# NFC_led_bar.net
KiCad netlist of a schematic drawn in EAGLE
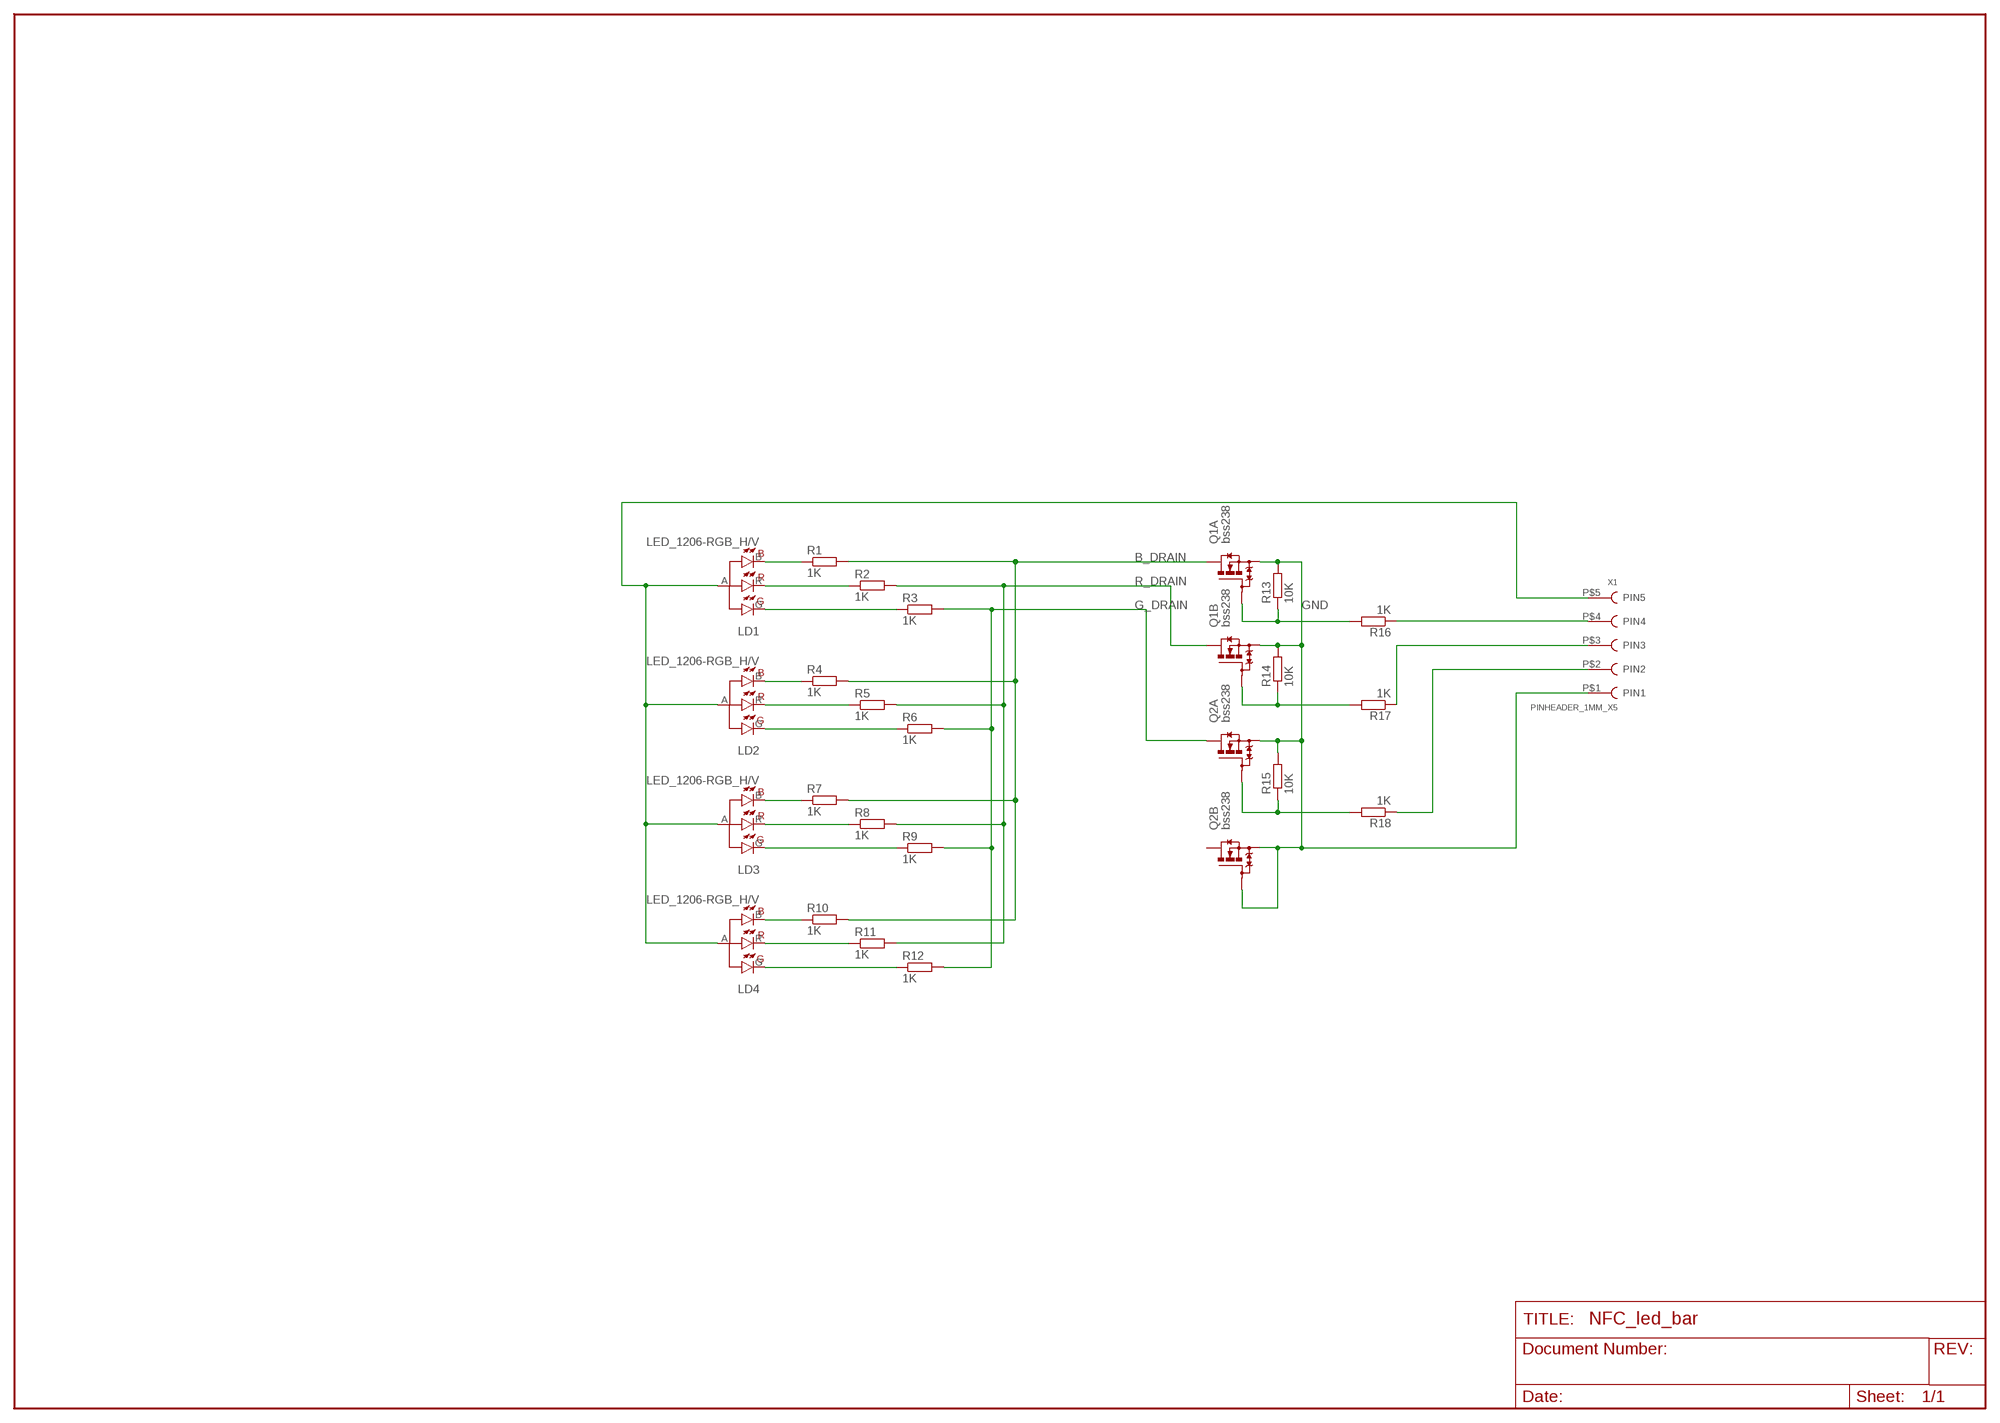
[diagram p0: schematic, sheet 1]

(export (version "E")
  (design (tool "Eeschema 10.0.6"))
  (components
    (comp (ref "LD1")
      (value "LED_1206-RGB_H/V")
      (footprint "eagle-import:RGB_1206_LED")
      (libsource (lib "eagle-import") (part "LED_1206-RGB_H/V"))
    )
    (comp (ref "LD2")
      (value "LED_1206-RGB_H/V")
      (footprint "eagle-import:RGB_1206_LED")
      (libsource (lib "eagle-import") (part "LED_1206-RGB_H/V"))
    )
    (comp (ref "LD3")
      (value "LED_1206-RGB_H/V")
      (footprint "eagle-import:RGB_1206_LED")
      (libsource (lib "eagle-import") (part "LED_1206-RGB_H/V"))
    )
    (comp (ref "LD4")
      (value "LED_1206-RGB_H/V")
      (footprint "eagle-import:RGB_1206_LED")
      (libsource (lib "eagle-import") (part "LED_1206-RGB_H/V"))
    )
    (comp (ref "Q1")
      (value "bss238")
      (footprint "eagle-import:SOT363")
      (fields (field (name "MF") "ON SEMICONDUCTOR") (field (name "MPN") "NTJD5121NT1G"))
      (libsource (lib "eagle-import") (part "NTJD5121NT1G"))
    )
    (comp (ref "Q2")
      (value "bss238")
      (footprint "eagle-import:SOT363")
      (fields (field (name "MF") "ON SEMICONDUCTOR") (field (name "MPN") "NTJD5121NT1G"))
      (libsource (lib "eagle-import") (part "NTJD5121NT1G"))
    )
    (comp (ref "R1")
      (value "1K")
      (footprint "eagle-import:0603")
      (libsource (lib "eagle-import") (part "SMD_R0603"))
    )
    (comp (ref "R2")
      (value "1K")
      (footprint "eagle-import:0603")
      (libsource (lib "eagle-import") (part "SMD_R0603"))
    )
    (comp (ref "R3")
      (value "1K")
      (footprint "eagle-import:0603")
      (libsource (lib "eagle-import") (part "SMD_R0603"))
    )
    (comp (ref "R4")
      (value "1K")
      (footprint "eagle-import:0603")
      (libsource (lib "eagle-import") (part "SMD_R0603"))
    )
    (comp (ref "R5")
      (value "1K")
      (footprint "eagle-import:0603")
      (libsource (lib "eagle-import") (part "SMD_R0603"))
    )
    (comp (ref "R6")
      (value "1K")
      (footprint "eagle-import:0603")
      (libsource (lib "eagle-import") (part "SMD_R0603"))
    )
    (comp (ref "R7")
      (value "1K")
      (footprint "eagle-import:0603")
      (libsource (lib "eagle-import") (part "SMD_R0603"))
    )
    (comp (ref "R8")
      (value "1K")
      (footprint "eagle-import:0603")
      (libsource (lib "eagle-import") (part "SMD_R0603"))
    )
    (comp (ref "R9")
      (value "1K")
      (footprint "eagle-import:0603")
      (libsource (lib "eagle-import") (part "SMD_R0603"))
    )
    (comp (ref "R10")
      (value "1K")
      (footprint "eagle-import:0603")
      (libsource (lib "eagle-import") (part "SMD_R0603"))
    )
    (comp (ref "R11")
      (value "1K")
      (footprint "eagle-import:0603")
      (libsource (lib "eagle-import") (part "SMD_R0603"))
    )
    (comp (ref "R12")
      (value "1K")
      (footprint "eagle-import:0603")
      (libsource (lib "eagle-import") (part "SMD_R0603"))
    )
    (comp (ref "R13")
      (value "10K")
      (footprint "eagle-import:0603")
      (libsource (lib "eagle-import") (part "SMD_R0603"))
    )
    (comp (ref "R14")
      (value "10K")
      (footprint "eagle-import:0603")
      (libsource (lib "eagle-import") (part "SMD_R0603"))
    )
    (comp (ref "R15")
      (value "10K")
      (footprint "eagle-import:0603")
      (libsource (lib "eagle-import") (part "SMD_R0603"))
    )
    (comp (ref "R16")
      (value "1K")
      (footprint "eagle-import:0603")
      (libsource (lib "eagle-import") (part "SMD_R0603"))
    )
    (comp (ref "R17")
      (value "1K")
      (footprint "eagle-import:0603")
      (libsource (lib "eagle-import") (part "SMD_R0603"))
    )
    (comp (ref "R18")
      (value "1K")
      (footprint "eagle-import:0603")
      (libsource (lib "eagle-import") (part "SMD_R0603"))
    )
    (comp (ref "X1")
      (value "PINHEADER_1MM_X5")
      (footprint "eagle-import:PIN_1MM_X5")
      (libsource (lib "eagle-import") (part "PINHEADER_1MM_X5"))
    )
  )
  (nets
    (net (code "1") (name "/B_DRAIN") (class "Default")
      (node (ref "Q1") (pin "6") (pinfunction "D_6") (pintype "passive"))
      (node (ref "R1") (pin "2") (pinfunction "2_2") (pintype "passive"))
      (node (ref "R10") (pin "2") (pinfunction "2_2") (pintype "passive"))
      (node (ref "R4") (pin "2") (pinfunction "2_2") (pintype "passive"))
      (node (ref "R7") (pin "2") (pinfunction "2_2") (pintype "passive"))
    )
    (net (code "2") (name "/GND") (class "Default")
      (node (ref "Q1") (pin "1") (pinfunction "S_1") (pintype "passive"))
      (node (ref "Q1") (pin "4") (pinfunction "S_4") (pintype "passive"))
      (node (ref "Q2") (pin "1") (pinfunction "S_1") (pintype "passive"))
      (node (ref "Q2") (pin "4") (pinfunction "S_4") (pintype "passive"))
      (node (ref "Q2") (pin "5") (pinfunction "G_5") (pintype "passive"))
      (node (ref "R13") (pin "2") (pinfunction "2_2") (pintype "passive"))
      (node (ref "R14") (pin "2") (pinfunction "2_2") (pintype "passive"))
      (node (ref "R15") (pin "2") (pinfunction "2_2") (pintype "passive"))
      (node (ref "X1") (pin "P$1") (pinfunction "PIN1_P$1") (pintype "bidirectional"))
    )
    (net (code "3") (name "/G_DRAIN") (class "Default")
      (node (ref "Q2") (pin "6") (pinfunction "D_6") (pintype "passive"))
      (node (ref "R12") (pin "2") (pinfunction "2_2") (pintype "passive"))
      (node (ref "R3") (pin "2") (pinfunction "2_2") (pintype "passive"))
      (node (ref "R6") (pin "2") (pinfunction "2_2") (pintype "passive"))
      (node (ref "R9") (pin "2") (pinfunction "2_2") (pintype "passive"))
    )
    (net (code "4") (name "/R_DRAIN") (class "Default")
      (node (ref "Q1") (pin "3") (pinfunction "D_3") (pintype "passive"))
      (node (ref "R11") (pin "2") (pinfunction "2_2") (pintype "passive"))
      (node (ref "R2") (pin "2") (pinfunction "2_2") (pintype "passive"))
      (node (ref "R5") (pin "2") (pinfunction "2_2") (pintype "passive"))
      (node (ref "R8") (pin "2") (pinfunction "2_2") (pintype "passive"))
    )
    (net (code "5") (name "Net-(LD1-BC)") (class "Default")
      (node (ref "LD1") (pin "B") (pinfunction "BC_B") (pintype "passive"))
      (node (ref "R1") (pin "1") (pinfunction "1_1") (pintype "passive"))
    )
    (net (code "6") (name "Net-(LD1-GC)") (class "Default")
      (node (ref "LD1") (pin "G") (pinfunction "GC_G") (pintype "passive"))
      (node (ref "R3") (pin "1") (pinfunction "1_1") (pintype "passive"))
    )
    (net (code "7") (name "Net-(LD1-RC)") (class "Default")
      (node (ref "LD1") (pin "R") (pinfunction "RC_R") (pintype "passive"))
      (node (ref "R2") (pin "1") (pinfunction "1_1") (pintype "passive"))
    )
    (net (code "8") (name "Net-(LD2-BC)") (class "Default")
      (node (ref "LD2") (pin "B") (pinfunction "BC_B") (pintype "passive"))
      (node (ref "R4") (pin "1") (pinfunction "1_1") (pintype "passive"))
    )
    (net (code "9") (name "Net-(LD2-GC)") (class "Default")
      (node (ref "LD2") (pin "G") (pinfunction "GC_G") (pintype "passive"))
      (node (ref "R6") (pin "1") (pinfunction "1_1") (pintype "passive"))
    )
    (net (code "10") (name "Net-(LD2-RC)") (class "Default")
      (node (ref "LD2") (pin "R") (pinfunction "RC_R") (pintype "passive"))
      (node (ref "R5") (pin "1") (pinfunction "1_1") (pintype "passive"))
    )
    (net (code "11") (name "Net-(LD3-BC)") (class "Default")
      (node (ref "LD3") (pin "B") (pinfunction "BC_B") (pintype "passive"))
      (node (ref "R7") (pin "1") (pinfunction "1_1") (pintype "passive"))
    )
    (net (code "12") (name "Net-(LD3-GC)") (class "Default")
      (node (ref "LD3") (pin "G") (pinfunction "GC_G") (pintype "passive"))
      (node (ref "R9") (pin "1") (pinfunction "1_1") (pintype "passive"))
    )
    (net (code "13") (name "Net-(LD3-RC)") (class "Default")
      (node (ref "LD3") (pin "R") (pinfunction "RC_R") (pintype "passive"))
      (node (ref "R8") (pin "1") (pinfunction "1_1") (pintype "passive"))
    )
    (net (code "14") (name "Net-(LD4-BC)") (class "Default")
      (node (ref "LD4") (pin "B") (pinfunction "BC_B") (pintype "passive"))
      (node (ref "R10") (pin "1") (pinfunction "1_1") (pintype "passive"))
    )
    (net (code "15") (name "Net-(LD4-GC)") (class "Default")
      (node (ref "LD4") (pin "G") (pinfunction "GC_G") (pintype "passive"))
      (node (ref "R12") (pin "1") (pinfunction "1_1") (pintype "passive"))
    )
    (net (code "16") (name "Net-(LD4-RC)") (class "Default")
      (node (ref "LD4") (pin "R") (pinfunction "RC_R") (pintype "passive"))
      (node (ref "R11") (pin "1") (pinfunction "1_1") (pintype "passive"))
    )
    (net (code "17") (name "Net-(Q1A-G)") (class "Default")
      (node (ref "Q1") (pin "2") (pinfunction "G_2") (pintype "passive"))
      (node (ref "R13") (pin "1") (pinfunction "1_1") (pintype "passive"))
      (node (ref "R16") (pin "2") (pinfunction "2_2") (pintype "passive"))
    )
    (net (code "18") (name "Net-(Q1B-G)") (class "Default")
      (node (ref "Q1") (pin "5") (pinfunction "G_5") (pintype "passive"))
      (node (ref "R14") (pin "1") (pinfunction "1_1") (pintype "passive"))
      (node (ref "R17") (pin "2") (pinfunction "2_2") (pintype "passive"))
    )
    (net (code "19") (name "Net-(Q2A-G)") (class "Default")
      (node (ref "Q2") (pin "2") (pinfunction "G_2") (pintype "passive"))
      (node (ref "R15") (pin "1") (pinfunction "1_1") (pintype "passive"))
      (node (ref "R18") (pin "2") (pinfunction "2_2") (pintype "passive"))
    )
    (net (code "20") (name "Net-(X1-PIN2)") (class "Default")
      (node (ref "R18") (pin "1") (pinfunction "1_1") (pintype "passive"))
      (node (ref "X1") (pin "P$2") (pinfunction "PIN2_P$2") (pintype "bidirectional"))
    )
    (net (code "21") (name "Net-(X1-PIN3)") (class "Default")
      (node (ref "R17") (pin "1") (pinfunction "1_1") (pintype "passive"))
      (node (ref "X1") (pin "P$3") (pinfunction "PIN3_P$3") (pintype "bidirectional"))
    )
    (net (code "22") (name "Net-(X1-PIN4)") (class "Default")
      (node (ref "R16") (pin "1") (pinfunction "1_1") (pintype "passive"))
      (node (ref "X1") (pin "P$4") (pinfunction "PIN4_P$4") (pintype "bidirectional"))
    )
    (net (code "23") (name "Net-(X1-PIN5)") (class "Default")
      (node (ref "LD1") (pin "A") (pinfunction "A_A") (pintype "passive"))
      (node (ref "LD2") (pin "A") (pinfunction "A_A") (pintype "passive"))
      (node (ref "LD3") (pin "A") (pinfunction "A_A") (pintype "passive"))
      (node (ref "LD4") (pin "A") (pinfunction "A_A") (pintype "passive"))
      (node (ref "X1") (pin "P$5") (pinfunction "PIN5_P$5") (pintype "bidirectional"))
    )
    (net (code "24") (name "unconnected-(Q2B-D-Pad3)") (class "Default")
      (node (ref "Q2") (pin "3") (pinfunction "D_3") (pintype "passive"))
    )
  )
)
